# ExternalMotorControllerRev5.net
KiCad netlist of a schematic drawn in EAGLE
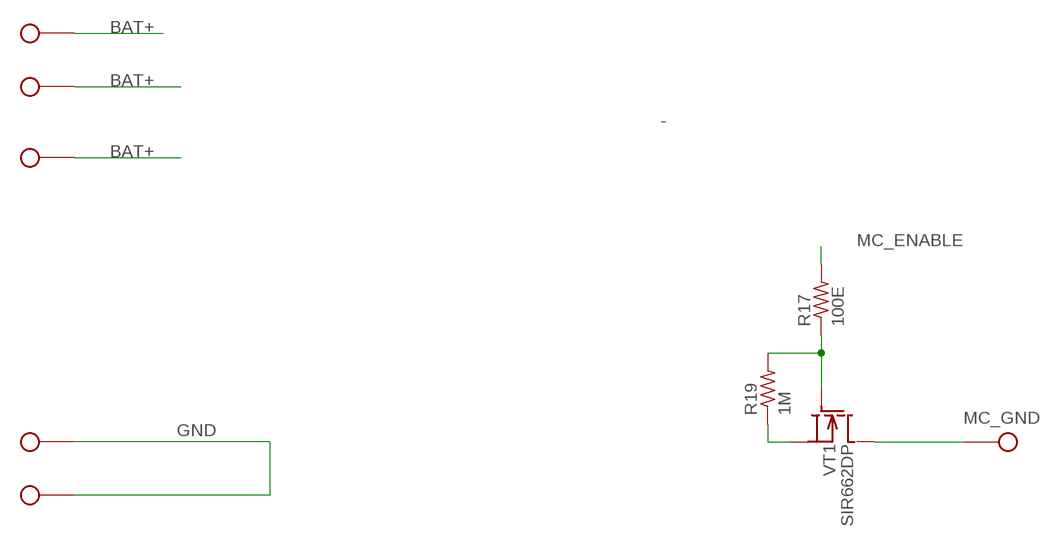
[diagram p0: schematic, sheet 1]
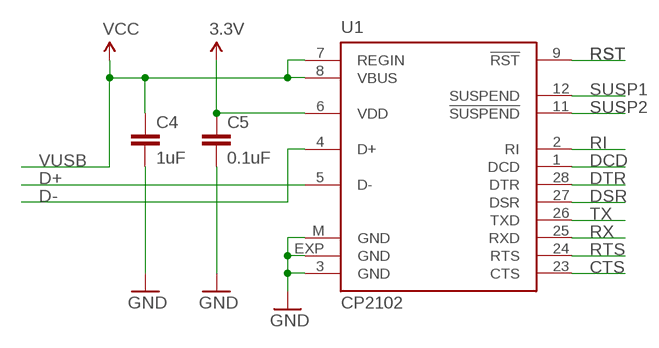
[diagram p1: schematic, sheet 2]
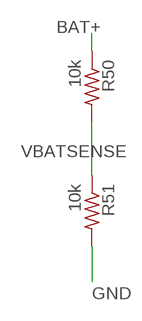
[diagram p2: schematic, sheet 3]
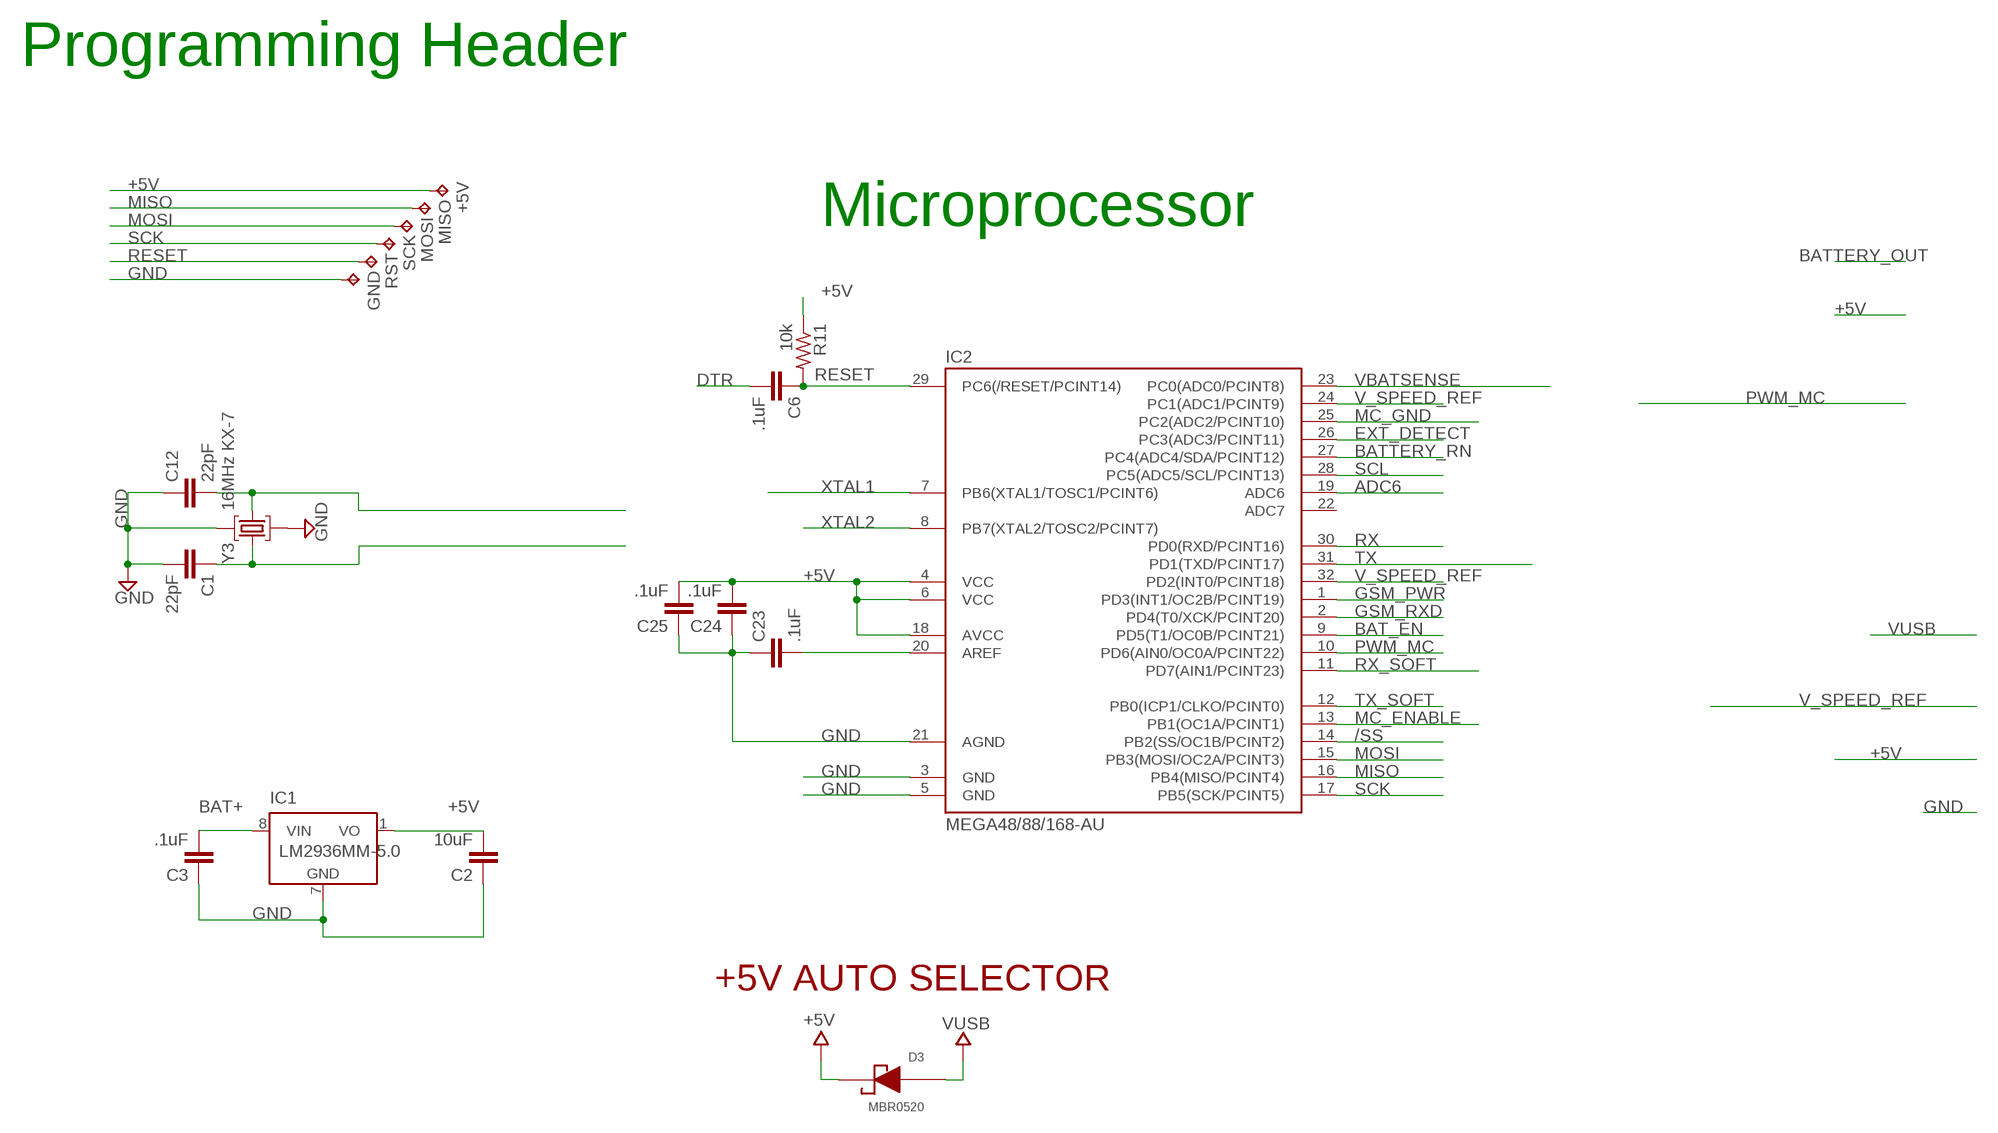
[diagram p3: schematic, sheet 7]

(export (version "E")
  (design (tool "Eeschema 10.0.6"))
  (components
    (comp (ref "R50")
      (value "10k")
      (footprint "eagle-import:R0402")
      (libsource (lib "eagle-import") (part "rcl_R-US_R0402"))
    )
    (comp (ref "R51")
      (value "10k")
      (footprint "eagle-import:R0402")
      (libsource (lib "eagle-import") (part "rcl_R-US_R0402"))
    )
    (comp (ref "R17")
      (value "100E")
      (footprint "eagle-import:R0402")
      (libsource (lib "eagle-import") (part "R-US_R0402"))
    )
    (comp (ref "R19")
      (value "1M")
      (footprint "eagle-import:R0402")
      (libsource (lib "eagle-import") (part "R-US_R0402"))
    )
    (comp (ref "VT1")
      (value "SIR662DP")
      (footprint "eagle-import:POWERPAK_SO8")
      (libsource (lib "eagle-import") (part "SIR662DP"))
    )
    (comp (ref "X1")
      (value "SOLDER_HOLE18AWG")
      (footprint "eagle-import:SOLDER_HOLE_18")
      (libsource (lib "eagle-import") (part "SOLDER_HOLE18AWG"))
    )
    (comp (ref "X2")
      (value "SOLDER_HOLE18AWG")
      (footprint "eagle-import:SOLDER_HOLE_18")
      (libsource (lib "eagle-import") (part "SOLDER_HOLE18AWG"))
    )
    (comp (ref "X3")
      (value "SOLDER_HOLE18AWG")
      (footprint "eagle-import:SOLDER_HOLE_18")
      (libsource (lib "eagle-import") (part "SOLDER_HOLE18AWG"))
    )
    (comp (ref "X4")
      (value "SOLDER_HOLE18AWG")
      (footprint "eagle-import:SOLDER_HOLE_18")
      (libsource (lib "eagle-import") (part "SOLDER_HOLE18AWG"))
    )
    (comp (ref "X5")
      (value "SOLDER_HOLE18AWG")
      (footprint "eagle-import:SOLDER_HOLE_18")
      (libsource (lib "eagle-import") (part "SOLDER_HOLE18AWG"))
    )
    (comp (ref "X13")
      (value "SOLDER_HOLE18AWG")
      (footprint "eagle-import:SOLDER_HOLE_18")
      (libsource (lib "eagle-import") (part "SOLDER_HOLE18AWG"))
    )
    (comp (ref "+5V")
      (value "TPTP08R")
      (footprint "eagle-import:TP08R")
      (libsource (lib "eagle-import") (part "TPTP08R"))
    )
    (comp (ref "C1")
      (value "22pF")
      (footprint "eagle-import:C0402")
      (libsource (lib "eagle-import") (part "rcl_C-EUC0402"))
    )
    (comp (ref "C2")
      (value "10uF")
      (footprint "eagle-import:C0805")
      (libsource (lib "eagle-import") (part "rcl_C-EUC0805"))
    )
    (comp (ref "C3")
      (value ".1uF")
      (footprint "eagle-import:C0402")
      (libsource (lib "eagle-import") (part "rcl_C-EUC0402"))
    )
    (comp (ref "C6")
      (value ".1uF")
      (footprint "eagle-import:C0402")
      (libsource (lib "eagle-import") (part "rcl_C-EUC0402"))
    )
    (comp (ref "C12")
      (value "22pF")
      (footprint "eagle-import:C0402")
      (libsource (lib "eagle-import") (part "C-EUC0402"))
    )
    (comp (ref "C23")
      (value ".1uF")
      (footprint "eagle-import:C0402")
      (libsource (lib "eagle-import") (part "rcl_C-EUC0402"))
    )
    (comp (ref "C24")
      (value ".1uF")
      (footprint "eagle-import:C0402")
      (libsource (lib "eagle-import") (part "rcl_C-EUC0402"))
    )
    (comp (ref "C25")
      (value ".1uF")
      (footprint "eagle-import:C0402")
      (libsource (lib "eagle-import") (part "rcl_C-EUC0402"))
    )
    (comp (ref "D3")
      (value "MBR0520")
      (footprint "eagle-import:SOD-123")
      (libsource (lib "eagle-import") (part "MBR0520"))
    )
    (comp (ref "GND")
      (value "TPTP10R")
      (footprint "eagle-import:TP10R")
      (libsource (lib "eagle-import") (part "TPTP10R"))
    )
    (comp (ref "IC1")
      (value "LM2936MM-5.0")
      (footprint "eagle-import:MINI-SO8")
      (fields (field (name "MF") "NATIONAL SEMICONDUCTOR") (field (name "MPN") "LM2936MM-5.0/NOPB"))
      (libsource (lib "eagle-import") (part "LM2936?MM-5.0"))
    )
    (comp (ref "IC2")
      (value "MEGA48/88/168-AU")
      (footprint "eagle-import:TQFP32-08")
      (libsource (lib "eagle-import") (part "MEGA48/88/168-AU"))
    )
    (comp (ref "MISO")
      (value "TPTP08R")
      (footprint "eagle-import:TP08R")
      (libsource (lib "eagle-import") (part "TPTP08R"))
    )
    (comp (ref "MOSI")
      (value "TPTP08R")
      (footprint "eagle-import:TP08R")
      (libsource (lib "eagle-import") (part "TPTP08R"))
    )
    (comp (ref "R11")
      (value "10k")
      (footprint "eagle-import:R0402")
      (libsource (lib "eagle-import") (part "rcl_R-US_R0402"))
    )
    (comp (ref "RST")
      (value "TPTP10R")
      (footprint "eagle-import:TP10R")
      (libsource (lib "eagle-import") (part "TPTP10R"))
    )
    (comp (ref "SCK")
      (value "TPTP08R")
      (footprint "eagle-import:TP08R")
      (libsource (lib "eagle-import") (part "TPTP08R"))
    )
    (comp (ref "Y3")
      (value "16MHz KX-7")
      (footprint "eagle-import:CRYSTAL-3.2-2.5")
      (libsource (lib "eagle-import") (part "CRYSTAL-3.2-2.5"))
    )
    (comp (ref "C4")
      (value "1uF")
      (footprint "eagle-import:C0402")
      (libsource (lib "eagle-import") (part "CAP0402"))
    )
    (comp (ref "C5")
      (value "0.1uF")
      (footprint "eagle-import:C0402")
      (libsource (lib "eagle-import") (part "CAP0402"))
    )
    (comp (ref "U1")
      (value "CP2102")
      (footprint "eagle-import:MLP28")
      (libsource (lib "eagle-import") (part "CP210X_USB_UART"))
    )
  )
  (nets
    (net (code "1") (name "+5V") (class "Default")
      (node (ref "+5V") (pin "TP") (pinfunction "TP_TP") (pintype "input"))
      (node (ref "C2") (pin "2") (pinfunction "2_2") (pintype "passive"))
      (node (ref "C24") (pin "2") (pinfunction "2_2") (pintype "passive"))
      (node (ref "C25") (pin "2") (pinfunction "2_2") (pintype "passive"))
      (node (ref "D3") (pin "1") (pinfunction "CA_1") (pintype "passive"))
      (node (ref "IC1") (pin "1") (pinfunction "VO_1") (pintype "passive"))
      (node (ref "IC2") (pin "18") (pinfunction "AVCC_18") (pintype "passive"))
      (node (ref "IC2") (pin "4") (pinfunction "VCC_4") (pintype "power_in"))
      (node (ref "IC2") (pin "6") (pinfunction "VCC_6") (pintype "power_in"))
      (node (ref "R11") (pin "1") (pinfunction "1_1") (pintype "passive"))
    )
    (net (code "2") (name "3.3V") (class "Default")
      (node (ref "C5") (pin "1") (pinfunction "1_1") (pintype "passive"))
      (node (ref "U1") (pin "6") (pinfunction "VDD_6") (pintype "power_in"))
    )
    (net (code "3") (name "ADC6") (class "Default")
      (node (ref "IC2") (pin "19") (pinfunction "ADC6_19") (pintype "passive"))
    )
    (net (code "4") (name "BAT+") (class "Default")
      (node (ref "C3") (pin "2") (pinfunction "2_2") (pintype "passive"))
      (node (ref "IC1") (pin "8") (pinfunction "VIN_8") (pintype "input"))
      (node (ref "R50") (pin "1") (pinfunction "1_1") (pintype "passive"))
      (node (ref "X1") (pin "1") (pinfunction "P$1_1") (pintype "bidirectional"))
      (node (ref "X3") (pin "1") (pinfunction "P$1_1") (pintype "bidirectional"))
      (node (ref "X4") (pin "1") (pinfunction "P$1_1") (pintype "bidirectional"))
    )
    (net (code "6") (name "BATTERY_RN") (class "Default")
      (node (ref "IC2") (pin "27") (pinfunction "PC4(ADC4/SDA/PCINT12)_27") (pintype "bidirectional"))
    )
    (net (code "7") (name "BAT_EN") (class "Default")
      (node (ref "IC2") (pin "9") (pinfunction "PD5(T1/OC0B/PCINT21)_9") (pintype "bidirectional"))
    )
    (net (code "8") (name "CTS") (class "Default")
      (node (ref "U1") (pin "23") (pinfunction "CTS_23") (pintype "input"))
    )
    (net (code "9") (name "D+") (class "Default")
      (node (ref "U1") (pin "5") (pinfunction "D-_5") (pintype "bidirectional"))
    )
    (net (code "10") (name "D-") (class "Default")
      (node (ref "U1") (pin "4") (pinfunction "D+_4") (pintype "bidirectional"))
    )
    (net (code "11") (name "DCD") (class "Default")
      (node (ref "U1") (pin "1") (pinfunction "DCD_1") (pintype "input"))
    )
    (net (code "12") (name "DSR") (class "Default")
      (node (ref "U1") (pin "27") (pinfunction "DSR_27") (pintype "input"))
    )
    (net (code "13") (name "DTR") (class "Default")
      (node (ref "C6") (pin "2") (pinfunction "2_2") (pintype "passive"))
      (node (ref "U1") (pin "28") (pinfunction "DTR_28") (pintype "output"))
    )
    (net (code "14") (name "EXT_DETECT") (class "Default")
      (node (ref "IC2") (pin "26") (pinfunction "PC3(ADC3/PCINT11)_26") (pintype "bidirectional"))
    )
    (net (code "15") (name "GND") (class "Default")
      (node (ref "C1") (pin "2") (pinfunction "2_2") (pintype "passive"))
      (node (ref "C12") (pin "1") (pinfunction "1_1") (pintype "passive"))
      (node (ref "C2") (pin "1") (pinfunction "1_1") (pintype "passive"))
      (node (ref "C23") (pin "1") (pinfunction "1_1") (pintype "passive"))
      (node (ref "C24") (pin "1") (pinfunction "1_1") (pintype "passive"))
      (node (ref "C25") (pin "1") (pinfunction "1_1") (pintype "passive"))
      (node (ref "C3") (pin "1") (pinfunction "1_1") (pintype "passive"))
      (node (ref "C4") (pin "2") (pinfunction "2_2") (pintype "passive"))
      (node (ref "C5") (pin "2") (pinfunction "2_2") (pintype "passive"))
      (node (ref "GND") (pin "TP") (pinfunction "TP_TP") (pintype "input"))
      (node (ref "IC1") (pin "7") (pinfunction "GND_7") (pintype "passive"))
      (node (ref "IC2") (pin "21") (pinfunction "AGND_21") (pintype "power_in"))
      (node (ref "IC2") (pin "3") (pinfunction "GND_3") (pintype "power_in"))
      (node (ref "IC2") (pin "5") (pinfunction "GND_5") (pintype "power_in"))
      (node (ref "R19") (pin "1") (pinfunction "1_1") (pintype "passive"))
      (node (ref "R51") (pin "2") (pinfunction "2_2") (pintype "passive"))
      (node (ref "U1") (pin "3") (pinfunction "GND_3") (pintype "power_in"))
      (node (ref "U1") (pin "EXP") (pinfunction "GND_EXP") (pintype "power_in"))
      (node (ref "U1") (pin "M") (pinfunction "GND_M") (pintype "power_in"))
      (node (ref "VT1") (pin "S1") (pinfunction "S_S1") (pintype "bidirectional"))
      (node (ref "VT1") (pin "S2") (pinfunction "S_S2") (pintype "bidirectional"))
      (node (ref "VT1") (pin "S3") (pinfunction "S_S3") (pintype "bidirectional"))
      (node (ref "X13") (pin "1") (pinfunction "P$1_1") (pintype "bidirectional"))
      (node (ref "X5") (pin "1") (pinfunction "P$1_1") (pintype "bidirectional"))
      (node (ref "Y3") (pin "2") (pinfunction "GND_2") (pintype "passive"))
      (node (ref "Y3") (pin "4") (pinfunction "GND_4") (pintype "passive"))
    )
    (net (code "16") (name "GSM_PWR") (class "Default")
      (node (ref "IC2") (pin "1") (pinfunction "PD3(INT1/OC2B/PCINT19)_1") (pintype "bidirectional"))
    )
    (net (code "17") (name "GSM_RXD") (class "Default")
      (node (ref "IC2") (pin "2") (pinfunction "PD4(T0/XCK/PCINT20)_2") (pintype "bidirectional"))
    )
    (net (code "18") (name "MC_ENABLE") (class "Default")
      (node (ref "IC2") (pin "13") (pinfunction "PB1(OC1A/PCINT1)_13") (pintype "bidirectional"))
      (node (ref "R17") (pin "2") (pinfunction "2_2") (pintype "passive"))
    )
    (net (code "19") (name "MC_GND") (class "Default")
      (node (ref "IC2") (pin "25") (pinfunction "PC2(ADC2/PCINT10)_25") (pintype "bidirectional"))
      (node (ref "VT1") (pin "D") (pinfunction "D_D") (pintype "bidirectional"))
      (node (ref "X2") (pin "1") (pinfunction "P$1_1") (pintype "bidirectional"))
    )
    (net (code "20") (name "MISO") (class "Default")
      (node (ref "IC2") (pin "16") (pinfunction "PB4(MISO/PCINT4)_16") (pintype "bidirectional"))
      (node (ref "MISO") (pin "TP") (pinfunction "TP_TP") (pintype "input"))
    )
    (net (code "21") (name "MOSI") (class "Default")
      (node (ref "IC2") (pin "15") (pinfunction "PB3(MOSI/OC2A/PCINT3)_15") (pintype "bidirectional"))
      (node (ref "MOSI") (pin "TP") (pinfunction "TP_TP") (pintype "input"))
    )
    (net (code "22") (name "Net-(IC2-AREF)") (class "Default")
      (node (ref "C23") (pin "2") (pinfunction "2_2") (pintype "passive"))
      (node (ref "IC2") (pin "20") (pinfunction "AREF_20") (pintype "passive"))
    )
    (net (code "23") (name "Net-(R17-Pad1)") (class "Default")
      (node (ref "R17") (pin "1") (pinfunction "1_1") (pintype "passive"))
      (node (ref "R19") (pin "2") (pinfunction "2_2") (pintype "passive"))
      (node (ref "VT1") (pin "G") (pinfunction "G_G") (pintype "bidirectional"))
    )
    (net (code "24") (name "PWM_MC") (class "Default")
      (node (ref "IC2") (pin "10") (pinfunction "PD6(AIN0/OC0A/PCINT22)_10") (pintype "bidirectional"))
    )
    (net (code "25") (name "RESET") (class "Default")
      (node (ref "C6") (pin "1") (pinfunction "1_1") (pintype "passive"))
      (node (ref "IC2") (pin "29") (pinfunction "PC6(/RESET/PCINT14)_29") (pintype "bidirectional"))
      (node (ref "R11") (pin "2") (pinfunction "2_2") (pintype "passive"))
      (node (ref "RST") (pin "TP") (pinfunction "TP_TP") (pintype "input"))
    )
    (net (code "26") (name "RI") (class "Default")
      (node (ref "U1") (pin "2") (pinfunction "RI_2") (pintype "input"))
    )
    (net (code "27") (name "RST") (class "Default")
      (node (ref "U1") (pin "9") (pinfunction "~{RST}_9") (pintype "bidirectional"))
    )
    (net (code "28") (name "RTS") (class "Default")
      (node (ref "U1") (pin "24") (pinfunction "RTS_24") (pintype "output"))
    )
    (net (code "29") (name "RX") (class "Default")
      (node (ref "IC2") (pin "30") (pinfunction "PD0(RXD/PCINT16)_30") (pintype "bidirectional"))
      (node (ref "U1") (pin "25") (pinfunction "RXD_25") (pintype "input"))
    )
    (net (code "30") (name "RX_SOFT") (class "Default")
      (node (ref "IC2") (pin "11") (pinfunction "PD7(AIN1/PCINT23)_11") (pintype "bidirectional"))
    )
    (net (code "31") (name "SCK") (class "Default")
      (node (ref "IC2") (pin "17") (pinfunction "PB5(SCK/PCINT5)_17") (pintype "bidirectional"))
      (node (ref "SCK") (pin "TP") (pinfunction "TP_TP") (pintype "input"))
    )
    (net (code "32") (name "SCL") (class "Default")
      (node (ref "IC2") (pin "28") (pinfunction "PC5(ADC5/SCL/PCINT13)_28") (pintype "bidirectional"))
    )
    (net (code "33") (name "SUSP1") (class "Default")
      (node (ref "U1") (pin "12") (pinfunction "SUSPEND_12") (pintype "output"))
    )
    (net (code "34") (name "SUSP2") (class "Default")
      (node (ref "U1") (pin "11") (pinfunction "~{SUSPEND}_11") (pintype "output"))
    )
    (net (code "35") (name "TX") (class "Default")
      (node (ref "IC2") (pin "31") (pinfunction "PD1(TXD/PCINT17)_31") (pintype "bidirectional"))
      (node (ref "U1") (pin "26") (pinfunction "TXD_26") (pintype "output"))
    )
    (net (code "36") (name "TX_SOFT") (class "Default")
      (node (ref "IC2") (pin "12") (pinfunction "PB0(ICP1/CLKO/PCINT0)_12") (pintype "bidirectional"))
    )
    (net (code "37") (name "VBATSENSE") (class "Default")
      (node (ref "IC2") (pin "23") (pinfunction "PC0(ADC0/PCINT8)_23") (pintype "bidirectional"))
      (node (ref "R50") (pin "2") (pinfunction "2_2") (pintype "passive"))
      (node (ref "R51") (pin "1") (pinfunction "1_1") (pintype "passive"))
    )
    (net (code "38") (name "VUSB") (class "Default")
      (node (ref "C4") (pin "1") (pinfunction "1_1") (pintype "passive"))
      (node (ref "D3") (pin "2") (pinfunction "AN_2") (pintype "passive"))
      (node (ref "U1") (pin "7") (pinfunction "REGIN_7") (pintype "passive"))
      (node (ref "U1") (pin "8") (pinfunction "VBUS_8") (pintype "input"))
    )
    (net (code "39") (name "V_SPEED_REF") (class "Default")
      (node (ref "IC2") (pin "24") (pinfunction "PC1(ADC1/PCINT9)_24") (pintype "bidirectional"))
      (node (ref "IC2") (pin "32") (pinfunction "PD2(INT0/PCINT18)_32") (pintype "bidirectional"))
    )
    (net (code "40") (name "XTAL1") (class "Default")
      (node (ref "C12") (pin "2") (pinfunction "2_2") (pintype "passive"))
      (node (ref "IC2") (pin "7") (pinfunction "PB6(XTAL1/TOSC1/PCINT6)_7") (pintype "bidirectional"))
      (node (ref "Y3") (pin "1") (pinfunction "C1_1") (pintype "passive"))
    )
    (net (code "41") (name "XTAL2") (class "Default")
      (node (ref "C1") (pin "1") (pinfunction "1_1") (pintype "passive"))
      (node (ref "IC2") (pin "8") (pinfunction "PB7(XTAL2/TOSC2/PCINT7)_8") (pintype "bidirectional"))
      (node (ref "Y3") (pin "3") (pinfunction "C2_3") (pintype "passive"))
    )
    (net (code "42") (name "unconnected-(IC2-ADC7-Pad22)") (class "Default")
      (node (ref "IC2") (pin "22") (pinfunction "ADC7_22") (pintype "passive"))
    )
    (net (code "43") (name "{slash}SS") (class "Default")
      (node (ref "IC2") (pin "14") (pinfunction "PB2(SS/OC1B/PCINT2)_14") (pintype "bidirectional"))
    )
  )
)
